# LED_Matrix_3_4.net
KiCad netlist of a schematic drawn in EAGLE
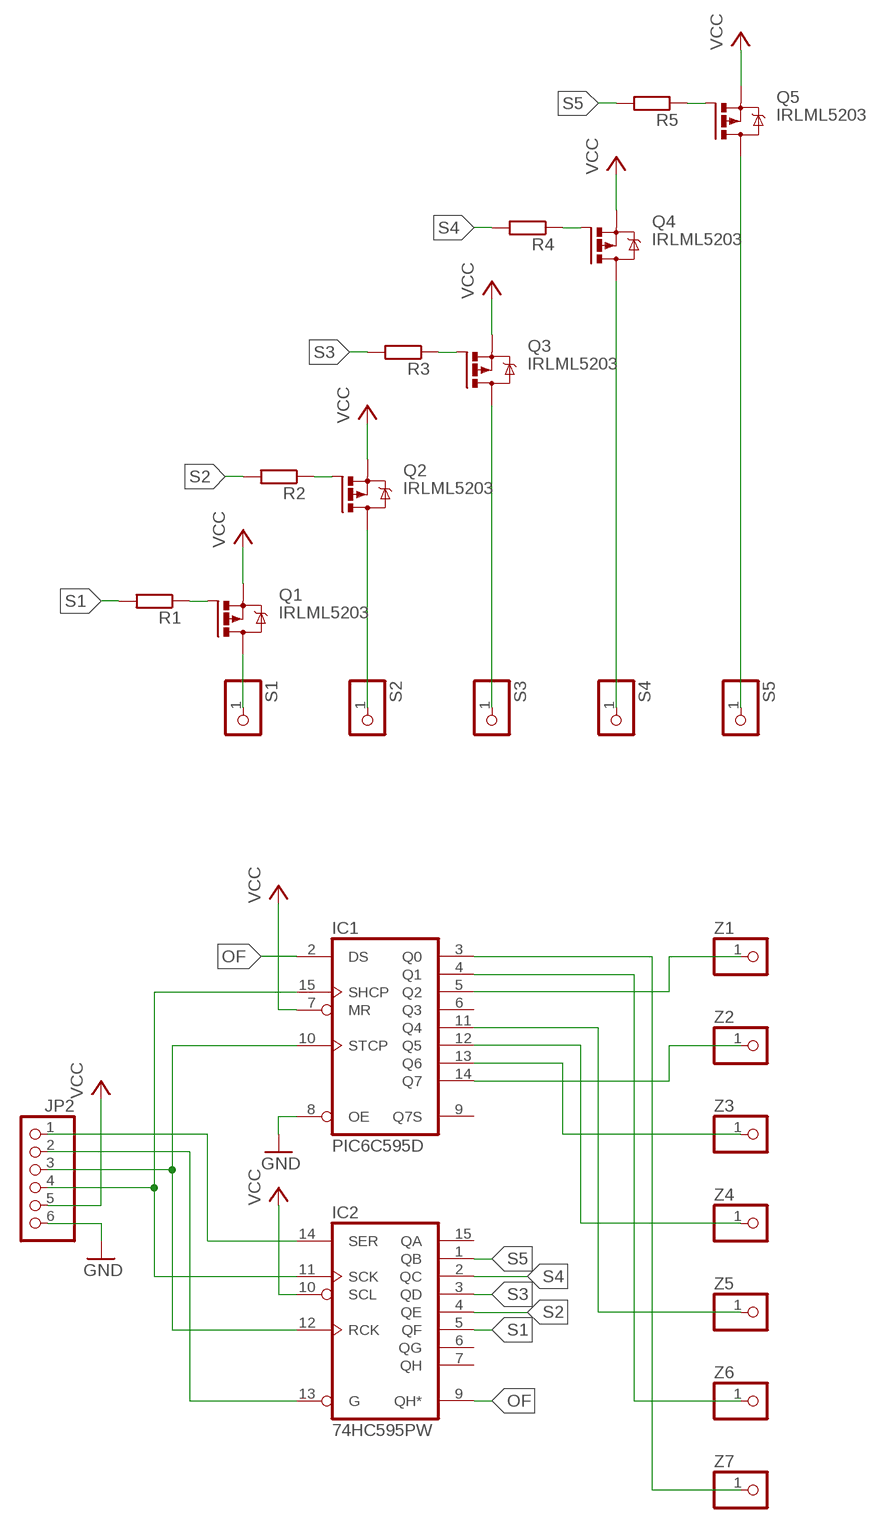
[diagram p0: schematic, sheet 1]

(export (version "E")
  (design (tool "Eeschema 10.0.6"))
  (components
    (comp (ref "IC1")
      (value "PIC6C595D")
      (footprint "eagle-import:SO16")
      (libsource (lib "eagle-import") (part "PIC6C595D"))
    )
    (comp (ref "IC2")
      (value "74HC595PW")
      (footprint "eagle-import:TSSOP16")
      (libsource (lib "eagle-import") (part "74595PWHC"))
    )
    (comp (ref "JP2")
      (value "PINHD-1X6")
      (footprint "eagle-import:1X06")
      (libsource (lib "eagle-import") (part "PINHD-1X6"))
    )
    (comp (ref "Q1")
      (value "IRLML5203")
      (footprint "eagle-import:MICRO3")
      (libsource (lib "eagle-import") (part "IRLML5203"))
    )
    (comp (ref "Q2")
      (value "IRLML5203")
      (footprint "eagle-import:MICRO3")
      (libsource (lib "eagle-import") (part "IRLML5203"))
    )
    (comp (ref "Q3")
      (value "IRLML5203")
      (footprint "eagle-import:MICRO3")
      (libsource (lib "eagle-import") (part "IRLML5203"))
    )
    (comp (ref "Q4")
      (value "IRLML5203")
      (footprint "eagle-import:MICRO3")
      (libsource (lib "eagle-import") (part "IRLML5203"))
    )
    (comp (ref "Q5")
      (value "IRLML5203")
      (footprint "eagle-import:MICRO3")
      (libsource (lib "eagle-import") (part "IRLML5203"))
    )
    (comp (ref "R1")
      (value "R-EU_R0603")
      (footprint "eagle-import:R0603")
      (libsource (lib "eagle-import") (part "R-EU_R0603"))
    )
    (comp (ref "R2")
      (value "R-EU_R0603")
      (footprint "eagle-import:R0603")
      (libsource (lib "eagle-import") (part "R-EU_R0603"))
    )
    (comp (ref "R3")
      (value "R-EU_R0603")
      (footprint "eagle-import:R0603")
      (libsource (lib "eagle-import") (part "R-EU_R0603"))
    )
    (comp (ref "R4")
      (value "R-EU_R0603")
      (footprint "eagle-import:R0603")
      (libsource (lib "eagle-import") (part "R-EU_R0603"))
    )
    (comp (ref "R5")
      (value "R-EU_R0603")
      (footprint "eagle-import:R0603")
      (libsource (lib "eagle-import") (part "R-EU_R0603"))
    )
    (comp (ref "S1")
      (value "PINHD-1X1")
      (footprint "eagle-import:1X01")
      (libsource (lib "eagle-import") (part "PINHD-1X1"))
    )
    (comp (ref "S2")
      (value "PINHD-1X1")
      (footprint "eagle-import:1X01")
      (libsource (lib "eagle-import") (part "PINHD-1X1"))
    )
    (comp (ref "S3")
      (value "PINHD-1X1")
      (footprint "eagle-import:1X01")
      (libsource (lib "eagle-import") (part "PINHD-1X1"))
    )
    (comp (ref "S4")
      (value "PINHD-1X1")
      (footprint "eagle-import:1X01")
      (libsource (lib "eagle-import") (part "PINHD-1X1"))
    )
    (comp (ref "S5")
      (value "PINHD-1X1")
      (footprint "eagle-import:1X01")
      (libsource (lib "eagle-import") (part "PINHD-1X1"))
    )
    (comp (ref "Z1")
      (value "PINHD-1X1")
      (footprint "eagle-import:1X01")
      (libsource (lib "eagle-import") (part "PINHD-1X1"))
    )
    (comp (ref "Z2")
      (value "PINHD-1X1")
      (footprint "eagle-import:1X01")
      (libsource (lib "eagle-import") (part "PINHD-1X1"))
    )
    (comp (ref "Z3")
      (value "PINHD-1X1")
      (footprint "eagle-import:1X01")
      (libsource (lib "eagle-import") (part "PINHD-1X1"))
    )
    (comp (ref "Z4")
      (value "PINHD-1X1")
      (footprint "eagle-import:1X01")
      (libsource (lib "eagle-import") (part "PINHD-1X1"))
    )
    (comp (ref "Z5")
      (value "PINHD-1X1")
      (footprint "eagle-import:1X01")
      (libsource (lib "eagle-import") (part "PINHD-1X1"))
    )
    (comp (ref "Z6")
      (value "PINHD-1X1")
      (footprint "eagle-import:1X01")
      (libsource (lib "eagle-import") (part "PINHD-1X1"))
    )
    (comp (ref "Z7")
      (value "PINHD-1X1")
      (footprint "eagle-import:1X01")
      (libsource (lib "eagle-import") (part "PINHD-1X1"))
    )
  )
  (nets
    (net (code "1") (name "GND") (class "Default")
      (node (ref "IC1") (pin "8") (pinfunction "OE_8") (pintype "input"))
      (node (ref "JP2") (pin "6") (pinfunction "6_6") (pintype "passive"))
    )
    (net (code "2") (name "Net-(IC1A-Q0)") (class "Default")
      (node (ref "IC1") (pin "3") (pinfunction "Q0_3") (pintype "tri_state"))
      (node (ref "Z7") (pin "1") (pinfunction "1_1") (pintype "passive"))
    )
    (net (code "3") (name "Net-(IC1A-Q1)") (class "Default")
      (node (ref "IC1") (pin "4") (pinfunction "Q1_4") (pintype "tri_state"))
      (node (ref "Z6") (pin "1") (pinfunction "1_1") (pintype "passive"))
    )
    (net (code "4") (name "Net-(IC1A-Q2)") (class "Default")
      (node (ref "IC1") (pin "5") (pinfunction "Q2_5") (pintype "tri_state"))
      (node (ref "Z1") (pin "1") (pinfunction "1_1") (pintype "passive"))
    )
    (net (code "5") (name "Net-(IC1A-Q4)") (class "Default")
      (node (ref "IC1") (pin "11") (pinfunction "Q4_11") (pintype "tri_state"))
      (node (ref "Z5") (pin "1") (pinfunction "1_1") (pintype "passive"))
    )
    (net (code "6") (name "Net-(IC1A-Q5)") (class "Default")
      (node (ref "IC1") (pin "12") (pinfunction "Q5_12") (pintype "tri_state"))
      (node (ref "Z4") (pin "1") (pinfunction "1_1") (pintype "passive"))
    )
    (net (code "7") (name "Net-(IC1A-Q6)") (class "Default")
      (node (ref "IC1") (pin "13") (pinfunction "Q6_13") (pintype "tri_state"))
      (node (ref "Z3") (pin "1") (pinfunction "1_1") (pintype "passive"))
    )
    (net (code "8") (name "Net-(IC1A-Q7)") (class "Default")
      (node (ref "IC1") (pin "14") (pinfunction "Q7_14") (pintype "tri_state"))
      (node (ref "Z2") (pin "1") (pinfunction "1_1") (pintype "passive"))
    )
    (net (code "9") (name "Net-(IC1A-SHCP)") (class "Default")
      (node (ref "IC1") (pin "15") (pinfunction "SHCP_15") (pintype "input"))
      (node (ref "IC2") (pin "11") (pinfunction "SCK_11") (pintype "input"))
      (node (ref "JP2") (pin "4") (pinfunction "4_4") (pintype "passive"))
    )
    (net (code "10") (name "Net-(IC1A-STCP)") (class "Default")
      (node (ref "IC1") (pin "10") (pinfunction "STCP_10") (pintype "input"))
      (node (ref "IC2") (pin "12") (pinfunction "RCK_12") (pintype "input"))
      (node (ref "JP2") (pin "3") (pinfunction "3_3") (pintype "passive"))
    )
    (net (code "11") (name "Net-(IC2A-G)") (class "Default")
      (node (ref "IC2") (pin "13") (pinfunction "G_13") (pintype "input"))
      (node (ref "JP2") (pin "2") (pinfunction "2_2") (pintype "passive"))
    )
    (net (code "12") (name "Net-(IC2A-SER)") (class "Default")
      (node (ref "IC2") (pin "14") (pinfunction "SER_14") (pintype "input"))
      (node (ref "JP2") (pin "1") (pinfunction "1_1") (pintype "passive"))
    )
    (net (code "13") (name "Net-(Q1-D)") (class "Default")
      (node (ref "Q1") (pin "3") (pinfunction "D_3") (pintype "passive"))
      (node (ref "S1") (pin "1") (pinfunction "1_1") (pintype "passive"))
    )
    (net (code "14") (name "Net-(Q1-G)") (class "Default")
      (node (ref "Q1") (pin "1") (pinfunction "G_1") (pintype "passive"))
      (node (ref "R1") (pin "1") (pinfunction "1_1") (pintype "passive"))
    )
    (net (code "15") (name "Net-(Q2-D)") (class "Default")
      (node (ref "Q2") (pin "3") (pinfunction "D_3") (pintype "passive"))
      (node (ref "S2") (pin "1") (pinfunction "1_1") (pintype "passive"))
    )
    (net (code "16") (name "Net-(Q2-G)") (class "Default")
      (node (ref "Q2") (pin "1") (pinfunction "G_1") (pintype "passive"))
      (node (ref "R2") (pin "1") (pinfunction "1_1") (pintype "passive"))
    )
    (net (code "17") (name "Net-(Q3-D)") (class "Default")
      (node (ref "Q3") (pin "3") (pinfunction "D_3") (pintype "passive"))
      (node (ref "S3") (pin "1") (pinfunction "1_1") (pintype "passive"))
    )
    (net (code "18") (name "Net-(Q3-G)") (class "Default")
      (node (ref "Q3") (pin "1") (pinfunction "G_1") (pintype "passive"))
      (node (ref "R3") (pin "1") (pinfunction "1_1") (pintype "passive"))
    )
    (net (code "19") (name "Net-(Q4-D)") (class "Default")
      (node (ref "Q4") (pin "3") (pinfunction "D_3") (pintype "passive"))
      (node (ref "S4") (pin "1") (pinfunction "1_1") (pintype "passive"))
    )
    (net (code "20") (name "Net-(Q4-G)") (class "Default")
      (node (ref "Q4") (pin "1") (pinfunction "G_1") (pintype "passive"))
      (node (ref "R4") (pin "1") (pinfunction "1_1") (pintype "passive"))
    )
    (net (code "21") (name "Net-(Q5-D)") (class "Default")
      (node (ref "Q5") (pin "3") (pinfunction "D_3") (pintype "passive"))
      (node (ref "S5") (pin "1") (pinfunction "1_1") (pintype "passive"))
    )
    (net (code "22") (name "Net-(Q5-G)") (class "Default")
      (node (ref "Q5") (pin "1") (pinfunction "G_1") (pintype "passive"))
      (node (ref "R5") (pin "1") (pinfunction "1_1") (pintype "passive"))
    )
    (net (code "23") (name "OF") (class "Default")
      (node (ref "IC1") (pin "2") (pinfunction "DS_2") (pintype "input"))
      (node (ref "IC2") (pin "9") (pinfunction "QH*_9") (pintype "tri_state"))
    )
    (net (code "24") (name "S1") (class "Default")
      (node (ref "IC2") (pin "5") (pinfunction "QF_5") (pintype "tri_state"))
      (node (ref "R1") (pin "2") (pinfunction "2_2") (pintype "passive"))
    )
    (net (code "25") (name "S2") (class "Default")
      (node (ref "IC2") (pin "4") (pinfunction "QE_4") (pintype "tri_state"))
      (node (ref "R2") (pin "2") (pinfunction "2_2") (pintype "passive"))
    )
    (net (code "26") (name "S3") (class "Default")
      (node (ref "IC2") (pin "3") (pinfunction "QD_3") (pintype "tri_state"))
      (node (ref "R3") (pin "2") (pinfunction "2_2") (pintype "passive"))
    )
    (net (code "27") (name "S4") (class "Default")
      (node (ref "IC2") (pin "2") (pinfunction "QC_2") (pintype "tri_state"))
      (node (ref "R4") (pin "2") (pinfunction "2_2") (pintype "passive"))
    )
    (net (code "28") (name "S5") (class "Default")
      (node (ref "IC2") (pin "1") (pinfunction "QB_1") (pintype "tri_state"))
      (node (ref "R5") (pin "2") (pinfunction "2_2") (pintype "passive"))
    )
    (net (code "29") (name "VCC") (class "Default")
      (node (ref "IC1") (pin "7") (pinfunction "MR_7") (pintype "input"))
      (node (ref "IC2") (pin "10") (pinfunction "SCL_10") (pintype "input"))
      (node (ref "JP2") (pin "5") (pinfunction "5_5") (pintype "passive"))
      (node (ref "Q1") (pin "2") (pinfunction "S_2") (pintype "passive"))
      (node (ref "Q2") (pin "2") (pinfunction "S_2") (pintype "passive"))
      (node (ref "Q3") (pin "2") (pinfunction "S_2") (pintype "passive"))
      (node (ref "Q4") (pin "2") (pinfunction "S_2") (pintype "passive"))
      (node (ref "Q5") (pin "2") (pinfunction "S_2") (pintype "passive"))
    )
    (net (code "30") (name "unconnected-(IC1A-Q3-Pad6)") (class "Default")
      (node (ref "IC1") (pin "6") (pinfunction "Q3_6") (pintype "tri_state"))
    )
    (net (code "31") (name "unconnected-(IC1A-Q7S-Pad9)") (class "Default")
      (node (ref "IC1") (pin "9") (pinfunction "Q7S_9") (pintype "tri_state"))
    )
    (net (code "32") (name "unconnected-(IC2A-QA-Pad15)") (class "Default")
      (node (ref "IC2") (pin "15") (pinfunction "QA_15") (pintype "tri_state"))
    )
    (net (code "33") (name "unconnected-(IC2A-QG-Pad6)") (class "Default")
      (node (ref "IC2") (pin "6") (pinfunction "QG_6") (pintype "tri_state"))
    )
    (net (code "34") (name "unconnected-(IC2A-QH-Pad7)") (class "Default")
      (node (ref "IC2") (pin "7") (pinfunction "QH_7") (pintype "tri_state"))
    )
  )
)
